# bmsMaster_led.net
KiCad netlist of a schematic drawn in Altium Designer
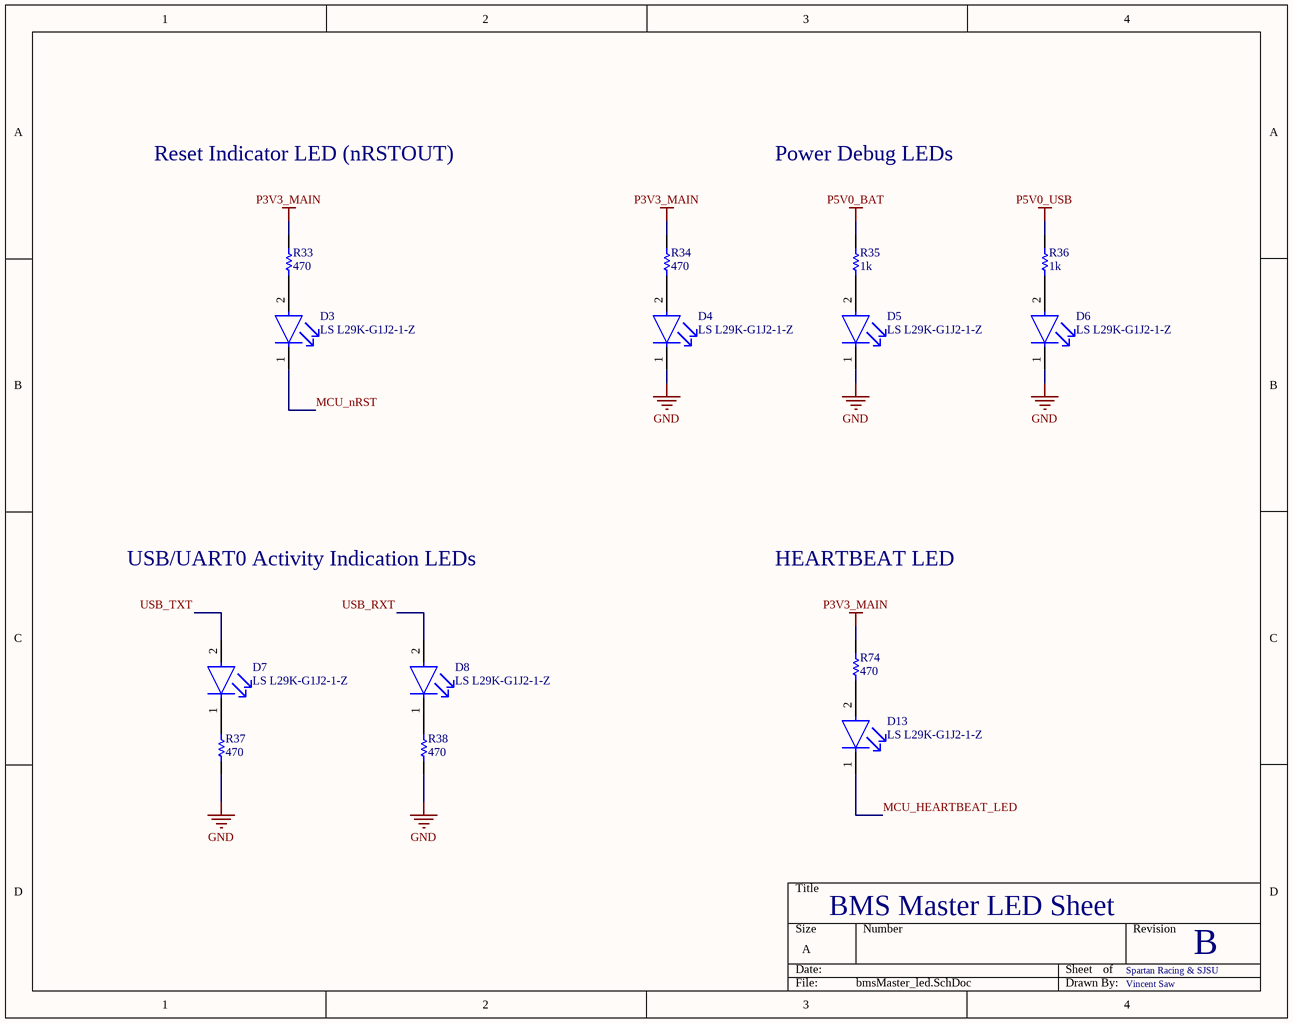
[diagram p0: bmsMaster_led.SchDoc]

(export (version "E")
  (design (tool "Eeschema 10.0.6"))
  (components
    (comp (ref "D3")
      (value "LS L29K-G1J2-1-Z")
      (footprint "FP-LS_L29K-MFG")
      (description "LED RED DIFFUSED 0603 SMD")
      (fields
        (field (name "MANUFACTURER") "Osram Opto")
        (field (name "OCTOPART") "https://octopart.com/ls+l29k-g1j2-1-z-osram+opto-31093939")
      )
      (libsource (lib "Altium Content Vault") (part "8706943c75ba83719d021d2fdc84c58"))
    )
    (comp (ref "D4")
      (value "LS L29K-G1J2-1-Z")
      (footprint "FP-LS_L29K-MFG")
      (description "LED RED DIFFUSED 0603 SMD")
      (fields
        (field (name "MANUFACTURER") "Osram Opto")
        (field (name "OCTOPART") "https://octopart.com/ls+l29k-g1j2-1-z-osram+opto-31093939")
      )
      (libsource (lib "Altium Content Vault") (part "8706943c75ba83719d021d2fdc84c58"))
    )
    (comp (ref "D5")
      (value "LS L29K-G1J2-1-Z")
      (footprint "FP-LS_L29K-MFG")
      (description "LED RED DIFFUSED 0603 SMD")
      (fields
        (field (name "MANUFACTURER") "Osram Opto")
        (field (name "OCTOPART") "https://octopart.com/ls+l29k-g1j2-1-z-osram+opto-31093939")
      )
      (libsource (lib "Altium Content Vault") (part "8706943c75ba83719d021d2fdc84c58"))
    )
    (comp (ref "D6")
      (value "LS L29K-G1J2-1-Z")
      (footprint "FP-LS_L29K-MFG")
      (description "LED RED DIFFUSED 0603 SMD")
      (fields
        (field (name "MANUFACTURER") "Osram Opto")
        (field (name "OCTOPART") "https://octopart.com/ls+l29k-g1j2-1-z-osram+opto-31093939")
      )
      (libsource (lib "Altium Content Vault") (part "8706943c75ba83719d021d2fdc84c58"))
    )
    (comp (ref "D7")
      (value "LS L29K-G1J2-1-Z")
      (footprint "FP-LS_L29K-MFG")
      (description "LED RED DIFFUSED 0603 SMD")
      (fields
        (field (name "MANUFACTURER") "Osram Opto")
        (field (name "OCTOPART") "https://octopart.com/ls+l29k-g1j2-1-z-osram+opto-31093939")
      )
      (libsource (lib "Altium Content Vault") (part "8706943c75ba83719d021d2fdc84c58"))
    )
    (comp (ref "D8")
      (value "LS L29K-G1J2-1-Z")
      (footprint "FP-LS_L29K-MFG")
      (description "LED RED DIFFUSED 0603 SMD")
      (fields
        (field (name "MANUFACTURER") "Osram Opto")
        (field (name "OCTOPART") "https://octopart.com/ls+l29k-g1j2-1-z-osram+opto-31093939")
      )
      (libsource (lib "Altium Content Vault") (part "8706943c75ba83719d021d2fdc84c58"))
    )
    (comp (ref "D13")
      (value "LS L29K-G1J2-1-Z")
      (footprint "FP-LS_L29K-MFG")
      (description "LED RED DIFFUSED 0603 SMD")
      (fields
        (field (name "MANUFACTURER") "Osram Opto")
        (field (name "OCTOPART") "https://octopart.com/ls+l29k-g1j2-1-z-osram+opto-31093939")
      )
      (libsource (lib "Altium Content Vault") (part "8706943c75ba83719d021d2fdc84c58"))
    )
    (comp (ref "R33")
      (value "470")
      (footprint "RESC1608X50N")
      (description "Resistor")
      (libsource (lib "Simulation Generic Components") (part "Resistor"))
    )
    (comp (ref "R34")
      (value "470")
      (footprint "RESC1608X50N")
      (description "Resistor")
      (libsource (lib "Simulation Generic Components") (part "Resistor"))
    )
    (comp (ref "R35")
      (value "1k")
      (footprint "RESC1608X50N")
      (description "Resistor")
      (libsource (lib "Simulation Generic Components") (part "Resistor"))
    )
    (comp (ref "R36")
      (value "1k")
      (footprint "RESC1608X50N")
      (description "Resistor")
      (libsource (lib "Simulation Generic Components") (part "Resistor"))
    )
    (comp (ref "R37")
      (value "470")
      (footprint "RESC1608X50N")
      (description "Resistor")
      (libsource (lib "Simulation Generic Components") (part "Resistor"))
    )
    (comp (ref "R38")
      (value "470")
      (footprint "RESC1608X50N")
      (description "Resistor")
      (libsource (lib "Simulation Generic Components") (part "Resistor"))
    )
    (comp (ref "R74")
      (value "470")
      (footprint "RESC1608X50N")
      (description "Resistor")
      (libsource (lib "Simulation Generic Components") (part "Resistor"))
    )
  )
  (nets
    (net (code "1") (name "/MCU_HEARTBEAT_LED") (class "Default")
      (node (ref "D13") (pin "1") (pinfunction "C_1") (pintype "passive"))
    )
    (net (code "2") (name "/MCU_nRST") (class "Default")
      (node (ref "D3") (pin "1") (pinfunction "C_1") (pintype "passive"))
    )
    (net (code "3") (name "/USB_RXT") (class "Default")
      (node (ref "D8") (pin "2") (pinfunction "A_2") (pintype "passive"))
    )
    (net (code "4") (name "/USB_TXT") (class "Default")
      (node (ref "D7") (pin "2") (pinfunction "A_2") (pintype "passive"))
    )
    (net (code "5") (name "GND") (class "Default")
      (node (ref "D4") (pin "1") (pinfunction "C_1") (pintype "passive"))
      (node (ref "D5") (pin "1") (pinfunction "C_1") (pintype "passive"))
      (node (ref "D6") (pin "1") (pinfunction "C_1") (pintype "passive"))
      (node (ref "R37") (pin "1") (pinfunction "1_1") (pintype "passive"))
      (node (ref "R38") (pin "1") (pinfunction "1_1") (pintype "passive"))
    )
    (net (code "6") (name "Net-(D3-A)") (class "Default")
      (node (ref "D3") (pin "2") (pinfunction "A_2") (pintype "passive"))
      (node (ref "R33") (pin "1") (pinfunction "1_1") (pintype "passive"))
    )
    (net (code "7") (name "Net-(D4-A)") (class "Default")
      (node (ref "D4") (pin "2") (pinfunction "A_2") (pintype "passive"))
      (node (ref "R34") (pin "1") (pinfunction "1_1") (pintype "passive"))
    )
    (net (code "8") (name "Net-(D5-A)") (class "Default")
      (node (ref "D5") (pin "2") (pinfunction "A_2") (pintype "passive"))
      (node (ref "R35") (pin "1") (pinfunction "1_1") (pintype "passive"))
    )
    (net (code "9") (name "Net-(D6-A)") (class "Default")
      (node (ref "D6") (pin "2") (pinfunction "A_2") (pintype "passive"))
      (node (ref "R36") (pin "1") (pinfunction "1_1") (pintype "passive"))
    )
    (net (code "10") (name "Net-(D7-C)") (class "Default")
      (node (ref "D7") (pin "1") (pinfunction "C_1") (pintype "passive"))
      (node (ref "R37") (pin "2") (pinfunction "2_2") (pintype "passive"))
    )
    (net (code "11") (name "Net-(D8-C)") (class "Default")
      (node (ref "D8") (pin "1") (pinfunction "C_1") (pintype "passive"))
      (node (ref "R38") (pin "2") (pinfunction "2_2") (pintype "passive"))
    )
    (net (code "12") (name "Net-(D13-A)") (class "Default")
      (node (ref "D13") (pin "2") (pinfunction "A_2") (pintype "passive"))
      (node (ref "R74") (pin "1") (pinfunction "1_1") (pintype "passive"))
    )
    (net (code "13") (name "P3V3_MAIN") (class "Default")
      (node (ref "R33") (pin "2") (pinfunction "2_2") (pintype "passive"))
      (node (ref "R34") (pin "2") (pinfunction "2_2") (pintype "passive"))
      (node (ref "R74") (pin "2") (pinfunction "2_2") (pintype "passive"))
    )
    (net (code "14") (name "P5V0_BAT") (class "Default")
      (node (ref "R35") (pin "2") (pinfunction "2_2") (pintype "passive"))
    )
    (net (code "15") (name "P5V0_USB") (class "Default")
      (node (ref "R36") (pin "2") (pinfunction "2_2") (pintype "passive"))
    )
  )
)
